# EM4095.net
KiCad netlist of a schematic drawn in Altium Designer
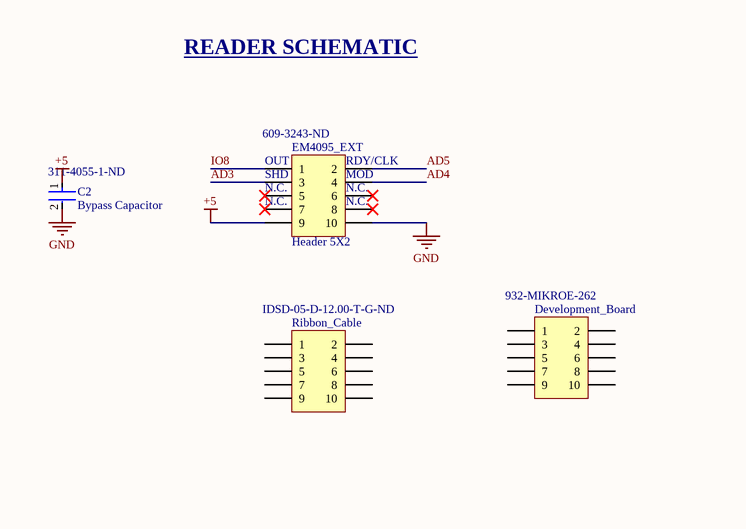
[diagram p0: EM4095.SchDoc, left]

(export (version "E")
  (design (tool "Eeschema 10.0.6"))
  (components
    (comp (ref "C2")
      (value "Bypass Capacitor")
      (footprint "FP-CC0603-DA-MFG")
      (description "CAP CER 0.1UF 10V X7R 0603")
      (fields
        (field (name "OCTOPART") "https://octopart.com/cc0603krx7r6bb104-yageo-9291607")
        (field (name "TOLERANCE") "0.1")
        (field (name "SUPPLIER PART NUMBER 1") "311-4055-1-ND")
      )
      (libsource (lib "Altium Content Vault") (part "11868f565c42a9108669ba33697ecf6"))
    )
    (comp (ref "Development_Board")
      (value "~")
      (footprint "HDR2X5")
      (description "EM4095 NFC/RFID Reader and Writer Development Board")
      (fields
        (field (name "SUPPLIER PART NUMBER 1") "932-MIKROE-262")
        (field (name "MANUFACTURER") "mikroElektronika")
        (field (name "MANUFACTURER PART NUMBER") "MIKROE-262")
      )
      (libsource (lib "Miscellaneous Connectors") (part "Header 5X2"))
    )
    (comp (ref "EM4095_EXT")
      (value "Header 5X2")
      (footprint "HDR2X5")
      (description "Board Connector, 66 Contact(s), 2 Row(s), Male, Straight, Solder Terminal")
      (fields
        (field (name "SUPPLIER PART NUMBER 1") "609-3243-ND")
        (field (name "MANUFACTURER") "Amphenol Communications Solutions")
        (field (name "MANUFACTURER PART NUMBER") "67997410HLF")
        (field (name "PUBLISHER") "Altium Limited")
      )
      (libsource (lib "Miscellaneous Connectors") (part "Header 5X2"))
    )
    (comp (ref "Ribbon_Cable")
      (value "~")
      (footprint "HDR2X5")
      (description "Cable Assembly, 28AWG")
      (fields
        (field (name "SUPPLIER PART NUMBER 1") "IDSD-05-D-12.00-T-G-ND")
        (field (name "MANUFACTURER") "Samtec")
        (field (name "MANUFACTURER PART NUMBER") "IDSD-05-D-12.00-T-G")
      )
      (libsource (lib "Miscellaneous Connectors") (part "Header 5X2"))
    )
  )
  (nets
    (net (code "1") (name "+5") (class "Default")
      (node (ref "C2") (pin "1") (pinfunction "1_1") (pintype "passive"))
      (node (ref "EM4095_EXT") (pin "9") (pinfunction "9_9") (pintype "passive"))
    )
    (net (code "2") (name "/AD3") (class "Default")
      (node (ref "EM4095_EXT") (pin "3") (pinfunction "3_3") (pintype "passive"))
    )
    (net (code "3") (name "/AD4") (class "Default")
      (node (ref "EM4095_EXT") (pin "4") (pinfunction "4_4") (pintype "passive"))
    )
    (net (code "4") (name "/AD5") (class "Default")
      (node (ref "EM4095_EXT") (pin "2") (pinfunction "2_2") (pintype "passive"))
    )
    (net (code "5") (name "/IO8") (class "Default")
      (node (ref "EM4095_EXT") (pin "1") (pinfunction "1_1") (pintype "passive"))
    )
    (net (code "6") (name "GND") (class "Default")
      (node (ref "C2") (pin "2") (pinfunction "2_2") (pintype "passive"))
      (node (ref "EM4095_EXT") (pin "10") (pinfunction "10_10") (pintype "passive"))
    )
    (net (code "7") (name "unconnected-(Development_Board-Pad1)") (class "Default")
      (node (ref "Development_Board") (pin "1") (pinfunction "1_1") (pintype "passive"))
    )
    (net (code "8") (name "unconnected-(Development_Board-Pad2)") (class "Default")
      (node (ref "Development_Board") (pin "2") (pinfunction "2_2") (pintype "passive"))
    )
    (net (code "9") (name "unconnected-(Development_Board-Pad3)") (class "Default")
      (node (ref "Development_Board") (pin "3") (pinfunction "3_3") (pintype "passive"))
    )
    (net (code "10") (name "unconnected-(Development_Board-Pad4)") (class "Default")
      (node (ref "Development_Board") (pin "4") (pinfunction "4_4") (pintype "passive"))
    )
    (net (code "11") (name "unconnected-(Development_Board-Pad5)") (class "Default")
      (node (ref "Development_Board") (pin "5") (pinfunction "5_5") (pintype "passive"))
    )
    (net (code "12") (name "unconnected-(Development_Board-Pad6)") (class "Default")
      (node (ref "Development_Board") (pin "6") (pinfunction "6_6") (pintype "passive"))
    )
    (net (code "13") (name "unconnected-(Development_Board-Pad7)") (class "Default")
      (node (ref "Development_Board") (pin "7") (pinfunction "7_7") (pintype "passive"))
    )
    (net (code "14") (name "unconnected-(Development_Board-Pad8)") (class "Default")
      (node (ref "Development_Board") (pin "8") (pinfunction "8_8") (pintype "passive"))
    )
    (net (code "15") (name "unconnected-(Development_Board-Pad9)") (class "Default")
      (node (ref "Development_Board") (pin "9") (pinfunction "9_9") (pintype "passive"))
    )
    (net (code "16") (name "unconnected-(Development_Board-Pad10)") (class "Default")
      (node (ref "Development_Board") (pin "10") (pinfunction "10_10") (pintype "passive"))
    )
    (net (code "17") (name "unconnected-(EM4095_EXT-Pad5)") (class "Default")
      (node (ref "EM4095_EXT") (pin "5") (pinfunction "5_5") (pintype "passive+no_connect"))
    )
    (net (code "18") (name "unconnected-(EM4095_EXT-Pad6)") (class "Default")
      (node (ref "EM4095_EXT") (pin "6") (pinfunction "6_6") (pintype "passive+no_connect"))
    )
    (net (code "19") (name "unconnected-(EM4095_EXT-Pad7)") (class "Default")
      (node (ref "EM4095_EXT") (pin "7") (pinfunction "7_7") (pintype "passive+no_connect"))
    )
    (net (code "20") (name "unconnected-(EM4095_EXT-Pad8)") (class "Default")
      (node (ref "EM4095_EXT") (pin "8") (pinfunction "8_8") (pintype "passive+no_connect"))
    )
    (net (code "21") (name "unconnected-(Ribbon_Cable-Pad1)") (class "Default")
      (node (ref "Ribbon_Cable") (pin "1") (pinfunction "1_1") (pintype "passive"))
    )
    (net (code "22") (name "unconnected-(Ribbon_Cable-Pad2)") (class "Default")
      (node (ref "Ribbon_Cable") (pin "2") (pinfunction "2_2") (pintype "passive"))
    )
    (net (code "23") (name "unconnected-(Ribbon_Cable-Pad3)") (class "Default")
      (node (ref "Ribbon_Cable") (pin "3") (pinfunction "3_3") (pintype "passive"))
    )
    (net (code "24") (name "unconnected-(Ribbon_Cable-Pad4)") (class "Default")
      (node (ref "Ribbon_Cable") (pin "4") (pinfunction "4_4") (pintype "passive"))
    )
    (net (code "25") (name "unconnected-(Ribbon_Cable-Pad5)") (class "Default")
      (node (ref "Ribbon_Cable") (pin "5") (pinfunction "5_5") (pintype "passive"))
    )
    (net (code "26") (name "unconnected-(Ribbon_Cable-Pad6)") (class "Default")
      (node (ref "Ribbon_Cable") (pin "6") (pinfunction "6_6") (pintype "passive"))
    )
    (net (code "27") (name "unconnected-(Ribbon_Cable-Pad7)") (class "Default")
      (node (ref "Ribbon_Cable") (pin "7") (pinfunction "7_7") (pintype "passive"))
    )
    (net (code "28") (name "unconnected-(Ribbon_Cable-Pad8)") (class "Default")
      (node (ref "Ribbon_Cable") (pin "8") (pinfunction "8_8") (pintype "passive"))
    )
    (net (code "29") (name "unconnected-(Ribbon_Cable-Pad9)") (class "Default")
      (node (ref "Ribbon_Cable") (pin "9") (pinfunction "9_9") (pintype "passive"))
    )
    (net (code "30") (name "unconnected-(Ribbon_Cable-Pad10)") (class "Default")
      (node (ref "Ribbon_Cable") (pin "10") (pinfunction "10_10") (pintype "passive"))
    )
  )
)
